# Single_RGB_Board.net
KiCad netlist of a schematic drawn in EAGLE
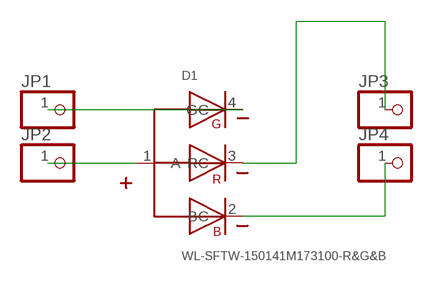
[diagram p0: schematic, sheet 1]

(export (version "E")
  (design (tool "Eeschema 10.0.6"))
  (components
    (comp (ref "D1")
      (value "WL-SFTW-150141M173100-R&G&B")
      (footprint "eagle-import:3528-COMMON-ANODE")
      (libsource (lib "eagle-import") (part "WL-SFTW-150141M173100-R&G&B"))
    )
    (comp (ref "JP1")
      (value "PINHD-1X1")
      (footprint "eagle-import:1X01")
      (libsource (lib "eagle-import") (part "PINHD-1X1"))
    )
    (comp (ref "JP2")
      (value "PINHD-1X1")
      (footprint "eagle-import:1X01")
      (libsource (lib "eagle-import") (part "PINHD-1X1"))
    )
    (comp (ref "JP3")
      (value "PINHD-1X1")
      (footprint "eagle-import:1X01")
      (libsource (lib "eagle-import") (part "PINHD-1X1"))
    )
    (comp (ref "JP4")
      (value "PINHD-1X1")
      (footprint "eagle-import:1X01")
      (libsource (lib "eagle-import") (part "PINHD-1X1"))
    )
  )
  (nets
    (net (code "1") (name "Net-(D1-A)") (class "Default")
      (node (ref "D1") (pin "1") (pinfunction "A_1") (pintype "bidirectional"))
      (node (ref "JP2") (pin "1") (pinfunction "1_1") (pintype "passive"))
    )
    (net (code "2") (name "Net-(D1-BC)") (class "Default")
      (node (ref "D1") (pin "2") (pinfunction "BC_2") (pintype "bidirectional"))
      (node (ref "JP4") (pin "1") (pinfunction "1_1") (pintype "passive"))
    )
    (net (code "3") (name "Net-(D1-GC)") (class "Default")
      (node (ref "D1") (pin "4") (pinfunction "GC_4") (pintype "bidirectional"))
      (node (ref "JP1") (pin "1") (pinfunction "1_1") (pintype "passive"))
    )
    (net (code "4") (name "Net-(D1-RC)") (class "Default")
      (node (ref "D1") (pin "3") (pinfunction "RC_3") (pintype "bidirectional"))
      (node (ref "JP3") (pin "1") (pinfunction "1_1") (pintype "passive"))
    )
  )
)
